# CAN.net
KiCad netlist of a schematic drawn in Altium Designer
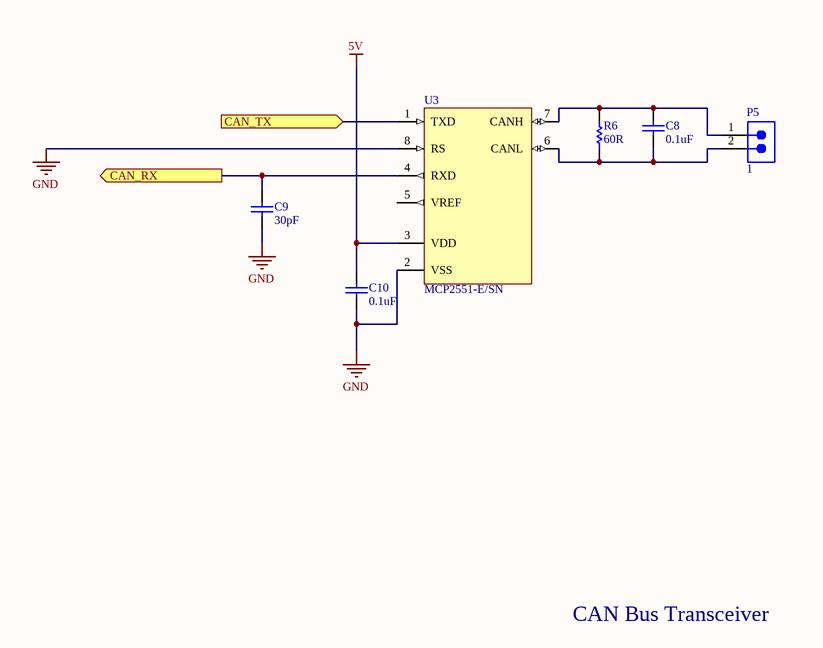
[diagram p0: CAN.SchDoc]

(export (version "E")
  (design (tool "Eeschema 10.0.6"))
  (components
    (comp (ref "C8")
      (value "0.1uF")
      (footprint "CAPC1608X90X35LL15T15")
      (description "Chip Capacitor, 100 nF, +/- 10%, 50 V, -55 to 125 degC, 0603 (1608 Metric), RoHS, Tape and Reel")
      (fields (field (name "TOLERANCE") "10%"))
      (libsource (lib "Altium Content Vault") (part "CAP-NP-2"))
    )
    (comp (ref "C9")
      (value "30pF")
      (footprint "CAPC1608X87X35LL15T15")
      (fields (field (name "MANUFACTURER") "Kemet") (field (name "PART NUMBER") "C0603C300J5GACTU"))
      (libsource (lib "Altium Content Vault") (part "CAP"))
    )
    (comp (ref "C10")
      (value "0.1uF")
      (footprint "CAPC1608X90X35LL15T15")
      (description "Chip Capacitor, 100 nF, +/- 10%, 50 V, -55 to 125 degC, 0603 (1608 Metric), RoHS, Tape and Reel")
      (fields (field (name "TOLERANCE") "10%"))
      (libsource (lib "Altium Content Vault") (part "CAP-NP-2"))
    )
    (comp (ref "P5")
      (value "1")
      (footprint "SMTC-DW-02-16-X-S-200")
      (fields (field (name "PARTNUMBER") "DW-02-16-G-S-200") (field (name "MANUFACTURER") "Samtec"))
      (libsource (lib "Altium Content Vault") (part "SMTC-DW-02-16-X-S-200"))
    )
    (comp (ref "R6")
      (value "60R")
      (footprint "RESC1609X50X30NL10T20")
      (fields (field (name "MANUFACTURER") "Vishay Dale") (field (name "PART NUMBER") "CRCW060310K0JNEA"))
      (libsource (lib "Altium Content Vault") (part "RES"))
    )
    (comp (ref "U3")
      (value "MCP2551-E/SN")
      (footprint "SOIC-SN8_N")
      (description "High-Speed CAN Transceiver, 8-Pin SOIC, Extended Temperature")
      (libsource (lib "Altium Content Vault") (part "COM-TRX-MCP2551-8"))
    )
  )
  (nets
    (net (code "1") (name "/CAN_RX") (class "Default")
      (node (ref "C9") (pin "2") (pinfunction "2_2") (pintype "passive"))
      (node (ref "U3") (pin "4") (pinfunction "RXD_4") (pintype "output"))
    )
    (net (code "2") (name "/CAN_TX") (class "Default")
      (node (ref "U3") (pin "1") (pinfunction "TXD_1") (pintype "input"))
    )
    (net (code "3") (name "5V") (class "Default")
      (node (ref "C10") (pin "2") (pinfunction "2_2") (pintype "passive"))
      (node (ref "U3") (pin "3") (pinfunction "VDD_3") (pintype "power_in"))
    )
    (net (code "4") (name "GND") (class "Default")
      (node (ref "C10") (pin "1") (pinfunction "1_1") (pintype "passive"))
      (node (ref "C9") (pin "1") (pinfunction "1_1") (pintype "passive"))
      (node (ref "U3") (pin "2") (pinfunction "VSS_2") (pintype "power_in"))
      (node (ref "U3") (pin "8") (pinfunction "RS_8") (pintype "input"))
    )
    (net (code "5") (name "Net-(U3-CANH)") (class "Default")
      (node (ref "C8") (pin "2") (pinfunction "2_2") (pintype "passive"))
      (node (ref "P5") (pin "1") (pinfunction "1_1") (pintype "passive"))
      (node (ref "R6") (pin "2") (pinfunction "2_2") (pintype "passive"))
      (node (ref "U3") (pin "7") (pinfunction "CANH_7") (pintype "bidirectional"))
    )
    (net (code "6") (name "Net-(U3-CANL)") (class "Default")
      (node (ref "C8") (pin "1") (pinfunction "1_1") (pintype "passive"))
      (node (ref "P5") (pin "2") (pinfunction "2_2") (pintype "passive"))
      (node (ref "R6") (pin "1") (pinfunction "1_1") (pintype "passive"))
      (node (ref "U3") (pin "6") (pinfunction "CANL_6") (pintype "bidirectional"))
    )
    (net (code "7") (name "unconnected-(U3-VREF-Pad5)") (class "Default")
      (node (ref "U3") (pin "5") (pinfunction "VREF_5") (pintype "output"))
    )
  )
)
